# ECE411-Group6-V4.net
KiCad netlist of a schematic drawn in EAGLE
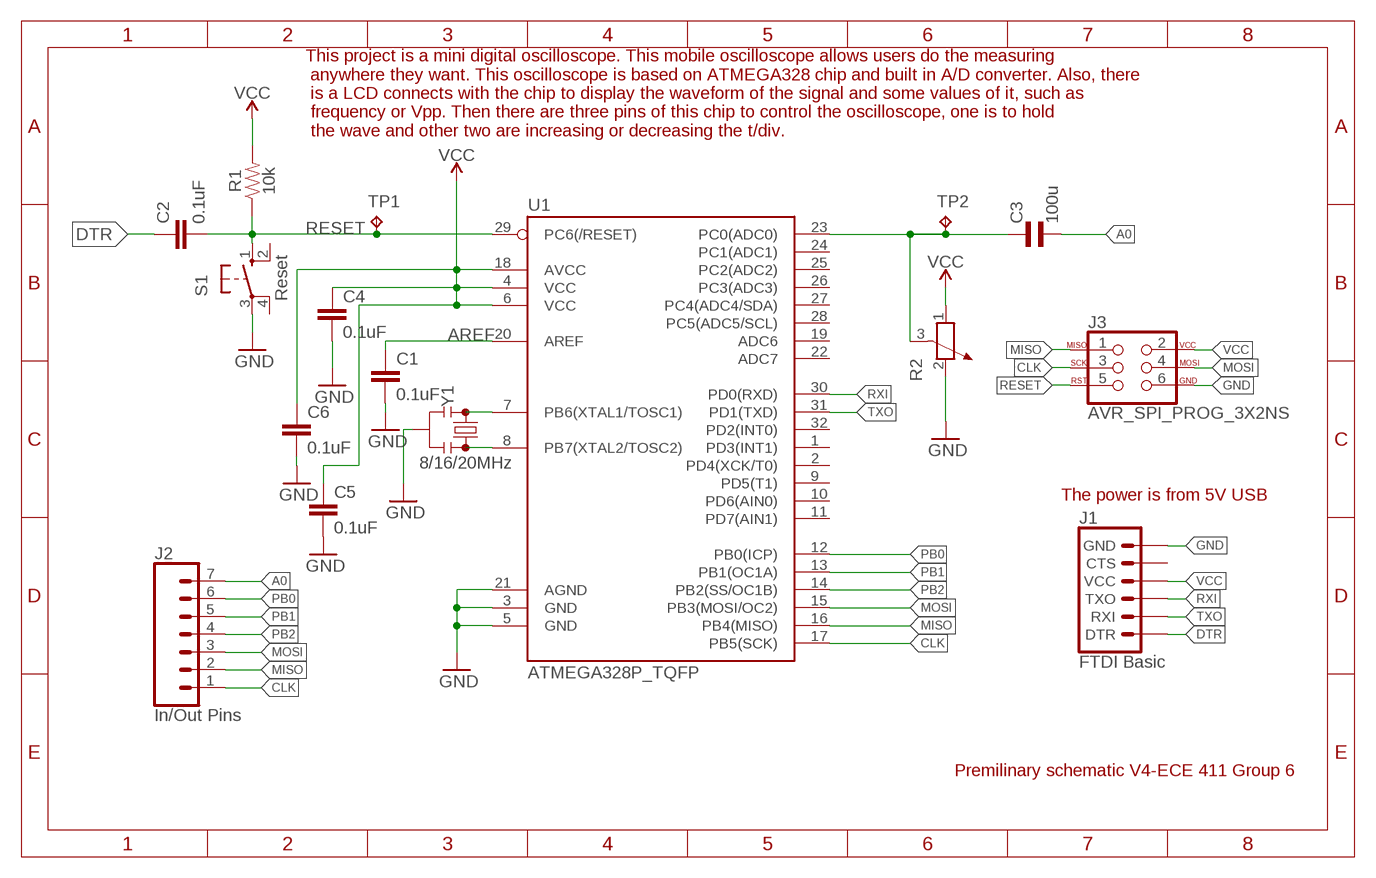
[diagram p0: schematic, sheet 1]

(export (version "E")
  (design (tool "Eeschema 10.0.6"))
  (components
    (comp (ref "C1")
      (value "0.1uF")
      (footprint "eagle-import:0603")
      (libsource (lib "eagle-import") (part "0.1UF-0603-25V-5%"))
    )
    (comp (ref "C2")
      (value "0.1uF")
      (footprint "eagle-import:0603")
      (libsource (lib "eagle-import") (part "0.1UF-0603-25V-5%"))
    )
    (comp (ref "C3")
      (value "100u")
      (footprint "eagle-import:EU25-10")
      (libsource (lib "eagle-import") (part "EL-BI25-10AXIAL"))
    )
    (comp (ref "C4")
      (value "0.1uF")
      (footprint "eagle-import:0603")
      (libsource (lib "eagle-import") (part "0.1UF-0603-25V-5%"))
    )
    (comp (ref "C5")
      (value "0.1uF")
      (footprint "eagle-import:0603")
      (libsource (lib "eagle-import") (part "0.1UF-0603-25V-5%"))
    )
    (comp (ref "C6")
      (value "0.1uF")
      (footprint "eagle-import:0603")
      (libsource (lib "eagle-import") (part "0.1UF-0603-25V-5%"))
    )
    (comp (ref "J1")
      (value "FTDI Basic")
      (footprint "eagle-import:1X06")
      (libsource (lib "eagle-import") (part "6_PIN_SERIAL_TARGET"))
    )
    (comp (ref "J2")
      (value "In/Out Pins")
      (footprint "eagle-import:1X07")
      (libsource (lib "eagle-import") (part "CONN_07"))
    )
    (comp (ref "J3")
      (value "AVR_SPI_PROG_3X2NS")
      (footprint "eagle-import:2X3-NS")
      (libsource (lib "eagle-import") (part "AVR_SPI_PROG_3X2NS"))
    )
    (comp (ref "R1")
      (value "10k")
      (footprint "eagle-import:0603")
      (libsource (lib "eagle-import") (part "10KOHM-0603-1/10W-1%"))
    )
    (comp (ref "R2")
      (value "POTENTIOMETER_PT-10")
      (footprint "eagle-import:PT-10")
      (libsource (lib "eagle-import") (part "POTENTIOMETER_PT-10"))
    )
    (comp (ref "S1")
      (value "Reset")
      (footprint "eagle-import:B3F-10XX")
      (fields (field (name "MPN") "B3F-1000"))
      (libsource (lib "eagle-import") (part "10-XX"))
    )
    (comp (ref "TP1")
      (value "TPB1,27")
      (footprint "eagle-import:B1,27")
      (libsource (lib "eagle-import") (part "TPB1,27"))
    )
    (comp (ref "TP2")
      (value "TPB1,27")
      (footprint "eagle-import:B1,27")
      (libsource (lib "eagle-import") (part "TPB1,27"))
    )
    (comp (ref "U1")
      (value "ATMEGA328P_TQFP")
      (footprint "eagle-import:TQFP32-08")
      (libsource (lib "eagle-import") (part "ATMEGA328P_TQFP"))
    )
    (comp (ref "Y1")
      (value "8/16/20MHz")
      (footprint "eagle-import:RESONATOR-SMD-3.2X1.3")
      (libsource (lib "eagle-import") (part "RESONATORSMD-3.2X1.3"))
    )
  )
  (nets
    (net (code "1") (name "/AREF") (class "Default")
      (node (ref "C1") (pin "1") (pinfunction "1_1") (pintype "passive"))
      (node (ref "U1") (pin "20") (pinfunction "AREF_20") (pintype "bidirectional"))
    )
    (net (code "2") (name "A0") (class "Default")
      (node (ref "C3") (pin "2") (pinfunction "2_2") (pintype "passive"))
      (node (ref "J2") (pin "7") (pinfunction "7_7") (pintype "passive"))
    )
    (net (code "3") (name "CLK") (class "Default")
      (node (ref "J2") (pin "1") (pinfunction "1_1") (pintype "passive"))
      (node (ref "J3") (pin "3") (pinfunction "3_3") (pintype "passive"))
      (node (ref "U1") (pin "17") (pinfunction "PB5(SCK)_17") (pintype "bidirectional"))
    )
    (net (code "4") (name "DTR") (class "Default")
      (node (ref "C2") (pin "1") (pinfunction "1_1") (pintype "passive"))
      (node (ref "J1") (pin "1") (pinfunction "DTR_1") (pintype "passive"))
    )
    (net (code "5") (name "GND") (class "Default")
      (node (ref "C1") (pin "2") (pinfunction "2_2") (pintype "passive"))
      (node (ref "C4") (pin "2") (pinfunction "2_2") (pintype "passive"))
      (node (ref "C5") (pin "2") (pinfunction "2_2") (pintype "passive"))
      (node (ref "C6") (pin "2") (pinfunction "2_2") (pintype "passive"))
      (node (ref "J1") (pin "6") (pinfunction "GND_6") (pintype "passive"))
      (node (ref "J3") (pin "6") (pinfunction "6_6") (pintype "passive"))
      (node (ref "R2") (pin "2") (pinfunction "2_2") (pintype "passive"))
      (node (ref "S1") (pin "3") (pinfunction "P_3") (pintype "passive"))
      (node (ref "U1") (pin "21") (pinfunction "AGND_21") (pintype "bidirectional"))
      (node (ref "U1") (pin "3") (pinfunction "GND_3") (pintype "bidirectional"))
      (node (ref "U1") (pin "5") (pinfunction "GND_5") (pintype "bidirectional"))
      (node (ref "Y1") (pin "2") (pinfunction "2_2") (pintype "passive"))
    )
    (net (code "6") (name "MISO") (class "Default")
      (node (ref "J2") (pin "2") (pinfunction "2_2") (pintype "passive"))
      (node (ref "J3") (pin "1") (pinfunction "1_1") (pintype "passive"))
      (node (ref "U1") (pin "16") (pinfunction "PB4(MISO)_16") (pintype "bidirectional"))
    )
    (net (code "7") (name "MOSI") (class "Default")
      (node (ref "J2") (pin "3") (pinfunction "3_3") (pintype "passive"))
      (node (ref "J3") (pin "4") (pinfunction "4_4") (pintype "passive"))
      (node (ref "U1") (pin "15") (pinfunction "PB3(MOSI/OC2)_15") (pintype "bidirectional"))
    )
    (net (code "8") (name "Net-(U1-PB6(XTAL1{slash}TOSC1))") (class "Default")
      (node (ref "U1") (pin "7") (pinfunction "PB6(XTAL1/TOSC1)_7") (pintype "bidirectional"))
      (node (ref "Y1") (pin "1") (pinfunction "1_1") (pintype "passive"))
    )
    (net (code "9") (name "Net-(U1-PB7(XTAL2{slash}TOSC2))") (class "Default")
      (node (ref "U1") (pin "8") (pinfunction "PB7(XTAL2/TOSC2)_8") (pintype "bidirectional"))
      (node (ref "Y1") (pin "3") (pinfunction "3_3") (pintype "passive"))
    )
    (net (code "10") (name "Net-(U1-PC0(ADC0))") (class "Default")
      (node (ref "C3") (pin "1") (pinfunction "1_1") (pintype "passive"))
      (node (ref "R2") (pin "3") (pinfunction "3_3") (pintype "passive"))
      (node (ref "TP2") (pin "TP") (pinfunction "TP_TP") (pintype "input"))
      (node (ref "U1") (pin "23") (pinfunction "PC0(ADC0)_23") (pintype "bidirectional"))
    )
    (net (code "11") (name "PB0") (class "Default")
      (node (ref "J2") (pin "6") (pinfunction "6_6") (pintype "passive"))
      (node (ref "U1") (pin "12") (pinfunction "PB0(ICP)_12") (pintype "bidirectional"))
    )
    (net (code "12") (name "PB1") (class "Default")
      (node (ref "J2") (pin "5") (pinfunction "5_5") (pintype "passive"))
      (node (ref "U1") (pin "13") (pinfunction "PB1(OC1A)_13") (pintype "bidirectional"))
    )
    (net (code "13") (name "PB2") (class "Default")
      (node (ref "J2") (pin "4") (pinfunction "4_4") (pintype "passive"))
      (node (ref "U1") (pin "14") (pinfunction "PB2(SS/OC1B)_14") (pintype "bidirectional"))
    )
    (net (code "14") (name "RESET") (class "Default")
      (node (ref "C2") (pin "2") (pinfunction "2_2") (pintype "passive"))
      (node (ref "J3") (pin "5") (pinfunction "5_5") (pintype "passive"))
      (node (ref "R1") (pin "1") (pinfunction "1_1") (pintype "passive"))
      (node (ref "S1") (pin "1") (pinfunction "S_1") (pintype "passive"))
      (node (ref "TP1") (pin "TP") (pinfunction "TP_TP") (pintype "input"))
      (node (ref "U1") (pin "29") (pinfunction "PC6(/RESET)_29") (pintype "bidirectional"))
    )
    (net (code "15") (name "RXI") (class "Default")
      (node (ref "J1") (pin "3") (pinfunction "TXO_3") (pintype "passive"))
      (node (ref "U1") (pin "30") (pinfunction "PD0(RXD)_30") (pintype "bidirectional"))
    )
    (net (code "16") (name "TXO") (class "Default")
      (node (ref "J1") (pin "2") (pinfunction "RXI_2") (pintype "passive"))
      (node (ref "U1") (pin "31") (pinfunction "PD1(TXD)_31") (pintype "bidirectional"))
    )
    (net (code "17") (name "VCC") (class "Default")
      (node (ref "C4") (pin "1") (pinfunction "1_1") (pintype "passive"))
      (node (ref "C5") (pin "1") (pinfunction "1_1") (pintype "passive"))
      (node (ref "C6") (pin "1") (pinfunction "1_1") (pintype "passive"))
      (node (ref "J1") (pin "4") (pinfunction "VCC_4") (pintype "passive"))
      (node (ref "J3") (pin "2") (pinfunction "2_2") (pintype "passive"))
      (node (ref "R1") (pin "2") (pinfunction "2_2") (pintype "passive"))
      (node (ref "R2") (pin "1") (pinfunction "1_1") (pintype "passive"))
      (node (ref "U1") (pin "18") (pinfunction "AVCC_18") (pintype "bidirectional"))
      (node (ref "U1") (pin "4") (pinfunction "VCC_4") (pintype "bidirectional"))
      (node (ref "U1") (pin "6") (pinfunction "VCC_6") (pintype "bidirectional"))
    )
    (net (code "18") (name "unconnected-(J1-CTS-Pad5)") (class "Default")
      (node (ref "J1") (pin "5") (pinfunction "CTS_5") (pintype "passive"))
    )
    (net (code "19") (name "unconnected-(S1-P1-Pad4)") (class "Default")
      (node (ref "S1") (pin "4") (pinfunction "P1_4") (pintype "passive"))
    )
    (net (code "20") (name "unconnected-(S1-S1-Pad2)") (class "Default")
      (node (ref "S1") (pin "2") (pinfunction "S1_2") (pintype "passive"))
    )
    (net (code "21") (name "unconnected-(U1-ADC6-Pad19)") (class "Default")
      (node (ref "U1") (pin "19") (pinfunction "ADC6_19") (pintype "bidirectional"))
    )
    (net (code "22") (name "unconnected-(U1-ADC7-Pad22)") (class "Default")
      (node (ref "U1") (pin "22") (pinfunction "ADC7_22") (pintype "bidirectional"))
    )
    (net (code "23") (name "unconnected-(U1-PC1(ADC1)-Pad24)") (class "Default")
      (node (ref "U1") (pin "24") (pinfunction "PC1(ADC1)_24") (pintype "bidirectional"))
    )
    (net (code "24") (name "unconnected-(U1-PC2(ADC2)-Pad25)") (class "Default")
      (node (ref "U1") (pin "25") (pinfunction "PC2(ADC2)_25") (pintype "bidirectional"))
    )
    (net (code "25") (name "unconnected-(U1-PC3(ADC3)-Pad26)") (class "Default")
      (node (ref "U1") (pin "26") (pinfunction "PC3(ADC3)_26") (pintype "bidirectional"))
    )
    (net (code "26") (name "unconnected-(U1-PC4(ADC4{slash}SDA)-Pad27)") (class "Default")
      (node (ref "U1") (pin "27") (pinfunction "PC4(ADC4/SDA)_27") (pintype "bidirectional"))
    )
    (net (code "27") (name "unconnected-(U1-PC5(ADC5{slash}SCL)-Pad28)") (class "Default")
      (node (ref "U1") (pin "28") (pinfunction "PC5(ADC5/SCL)_28") (pintype "bidirectional"))
    )
    (net (code "28") (name "unconnected-(U1-PD2(INT0)-Pad32)") (class "Default")
      (node (ref "U1") (pin "32") (pinfunction "PD2(INT0)_32") (pintype "bidirectional"))
    )
    (net (code "29") (name "unconnected-(U1-PD3(INT1)-Pad1)") (class "Default")
      (node (ref "U1") (pin "1") (pinfunction "PD3(INT1)_1") (pintype "bidirectional"))
    )
    (net (code "30") (name "unconnected-(U1-PD4(XCK{slash}T0)-Pad2)") (class "Default")
      (node (ref "U1") (pin "2") (pinfunction "PD4(XCK/T0)_2") (pintype "bidirectional"))
    )
    (net (code "31") (name "unconnected-(U1-PD5(T1)-Pad9)") (class "Default")
      (node (ref "U1") (pin "9") (pinfunction "PD5(T1)_9") (pintype "bidirectional"))
    )
    (net (code "32") (name "unconnected-(U1-PD6(AIN0)-Pad10)") (class "Default")
      (node (ref "U1") (pin "10") (pinfunction "PD6(AIN0)_10") (pintype "bidirectional"))
    )
    (net (code "33") (name "unconnected-(U1-PD7(AIN1)-Pad11)") (class "Default")
      (node (ref "U1") (pin "11") (pinfunction "PD7(AIN1)_11") (pintype "bidirectional"))
    )
  )
)
